# OctoSlime_TouchPad_Led_Mount.net
KiCad netlist of a schematic drawn in EasyEDA Pro
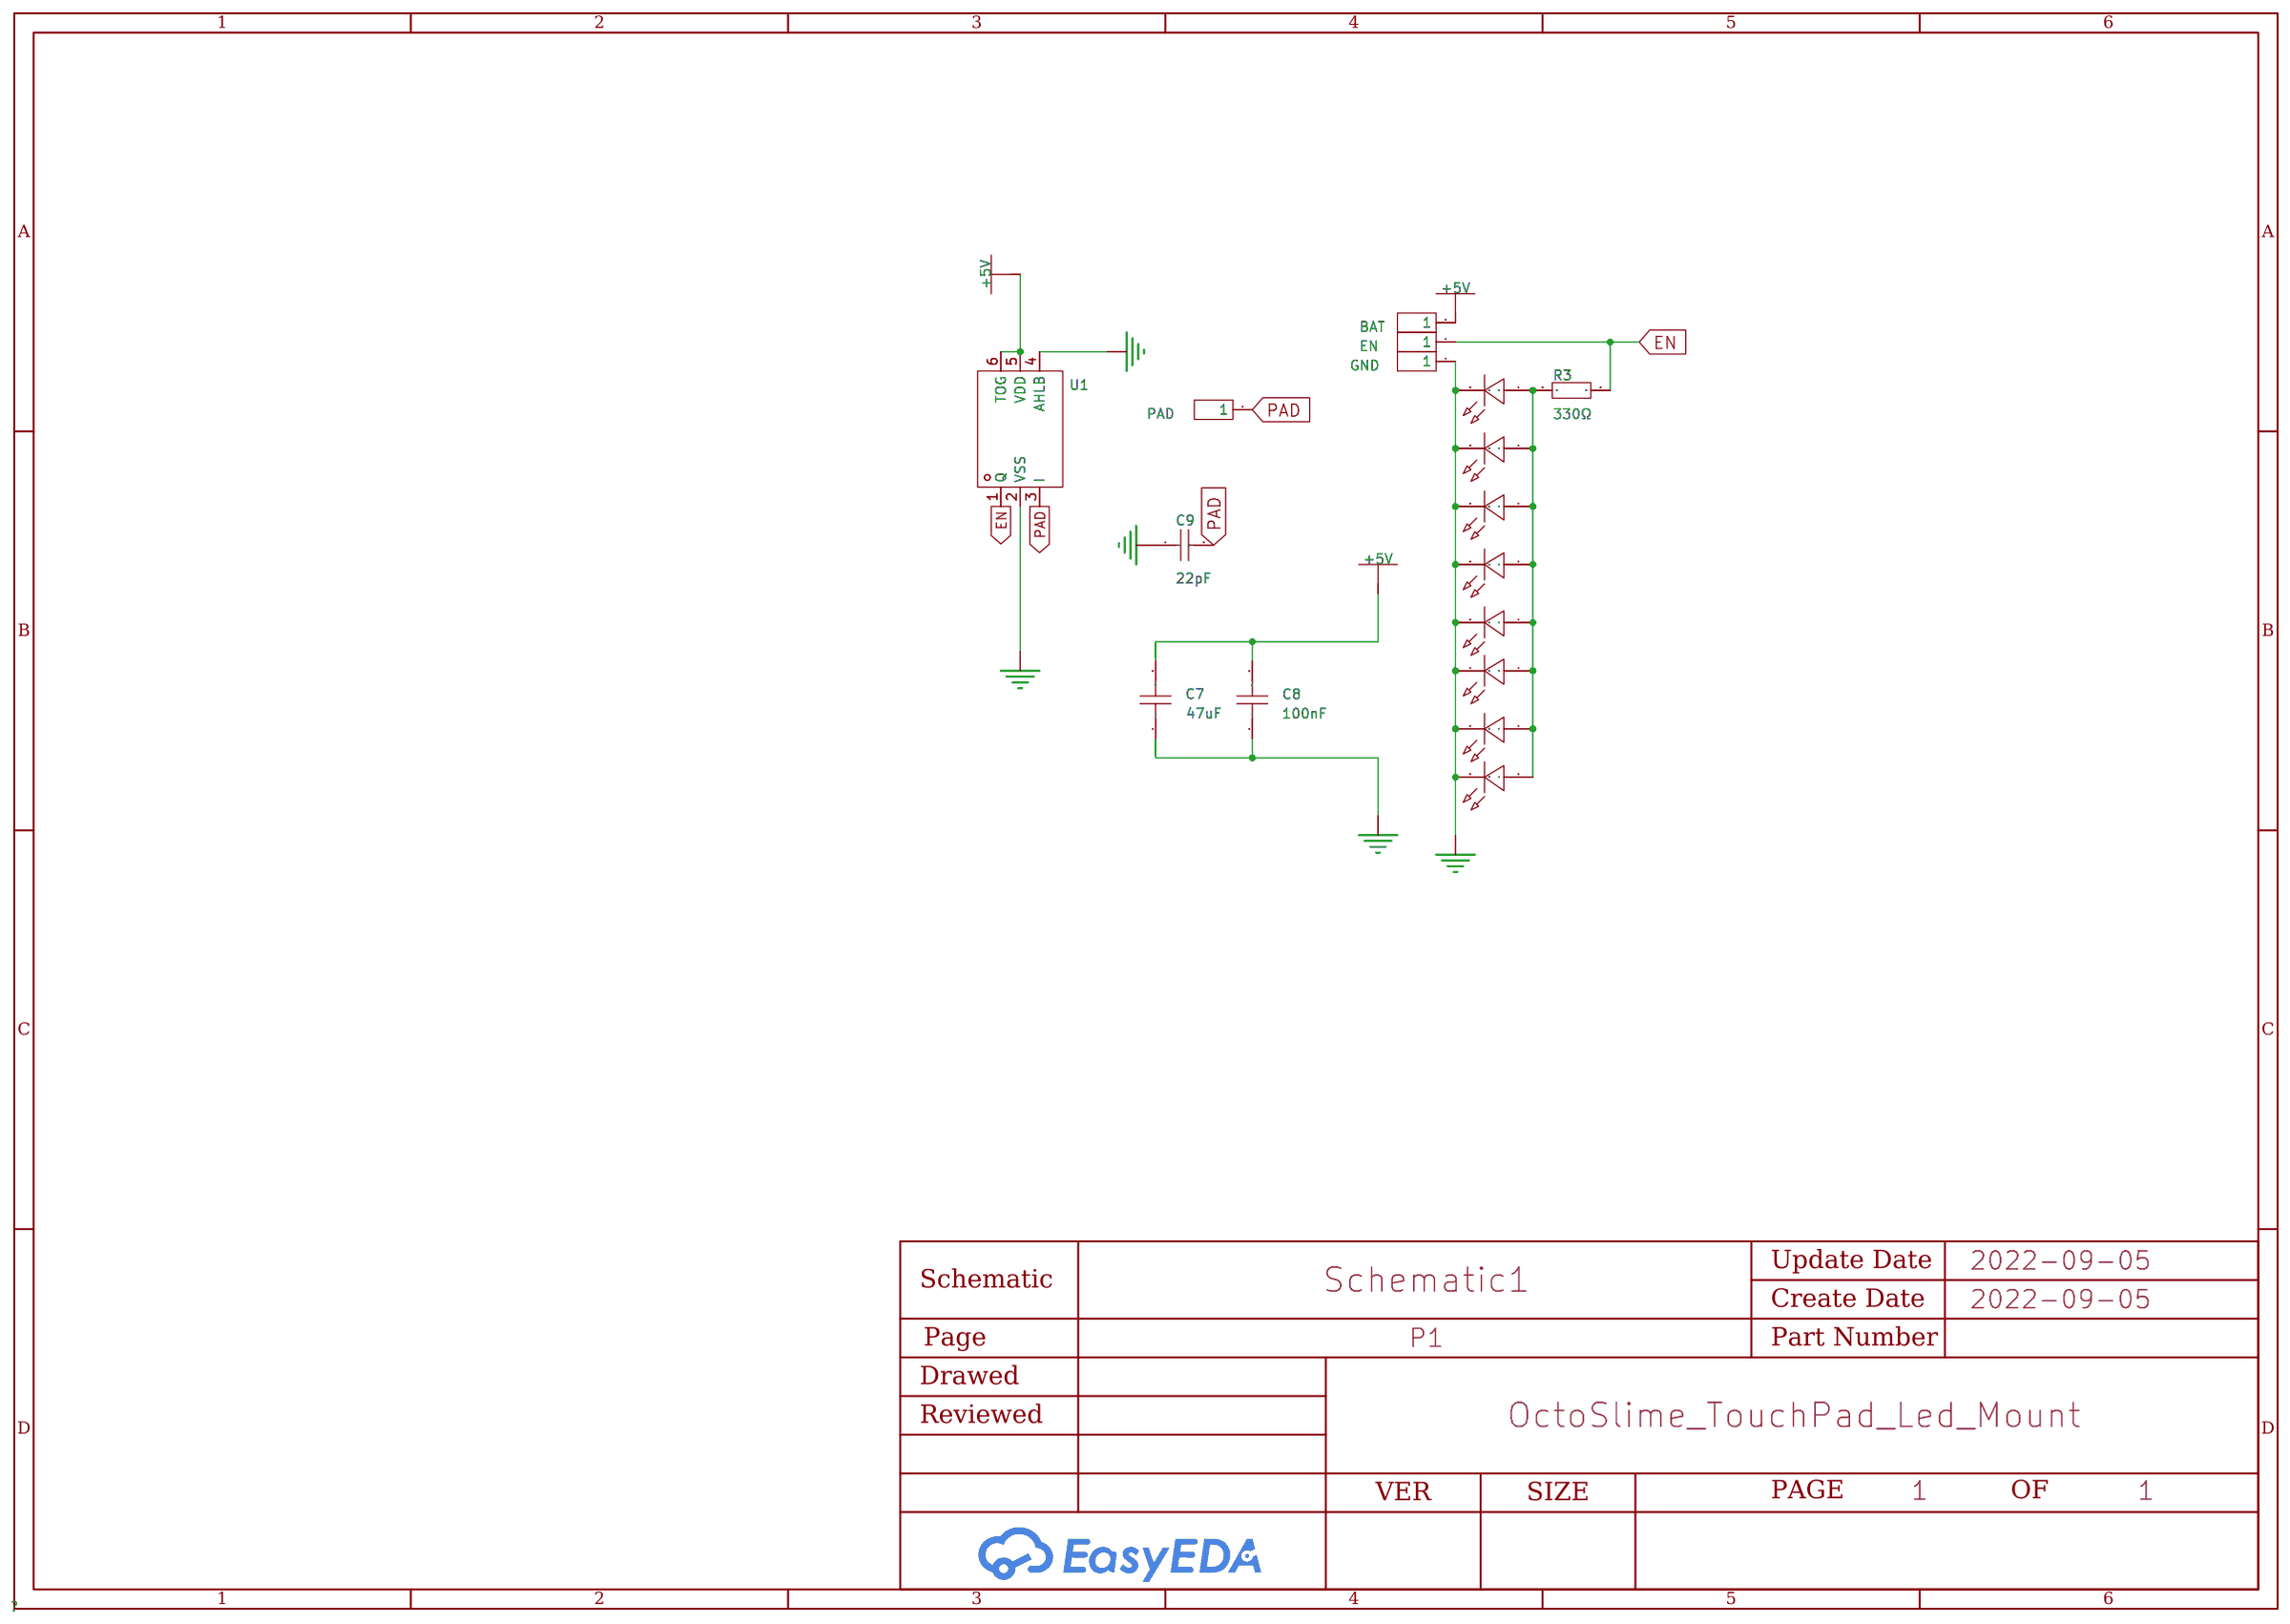
[diagram p0: schematic sheet]

(export (version "E")
  (design (tool "Eeschema 10.0.6"))
  (components
    (comp (ref "BAT")
      (value "~")
      (footprint "easyedapro:HDR-TH_1P-P2.54-V-M")
      (description "间距:-;总PIN位数:1;排数:1;插针结构:-;行距:-;安装类型:直插;圆针/方针:-;额定电流:-;额定电压:-;配合针长度:-;塑高:-;触头材质:-;触头镀层:-;颜色:黑色;")
      (fields (field (name "Manufacturer Part") "2.54-1*1P针") (field (name "Manufacturer") "BOOMELE(博穆精密)"))
      (libsource (lib "easyedapro") (part "Header-Male-2.54_1x1"))
    )
    (comp (ref "C7")
      (value "47uF")
      (footprint "easyedapro:C1206")
      (description "容值:47uF;精度:±20%;额定电压:10V;温度系数:X5R;")
      (fields
        (field (name "Manufacturer Part") "CL31A476MPHNNNE")
        (field (name "Manufacturer") "SAMSUNG(三星)")
      )
      (libsource (lib "easyedapro") (part "CL31A476MPHNNNE"))
    )
    (comp (ref "C8")
      (value "100nF")
      (footprint "easyedapro:C0402")
      (description "容值:100nF;精度:±10%;额定电压:50V;温度系数:X7R;")
      (fields
        (field (name "Manufacturer Part") "CL05B104KB54PNC")
        (field (name "Manufacturer") "SAMSUNG(三星)")
      )
      (libsource (lib "easyedapro") (part "CL05B104KB54PNC"))
    )
    (comp (ref "C9")
      (value "22pF")
      (footprint "easyedapro:C0805")
      (description "容值:22pF;精度:±5%;额定电压:50V;温度系数:C0G;")
      (fields
        (field (name "Manufacturer Part") "CL21C220JBANNNC")
        (field (name "Manufacturer") "SAMSUNG(三星)")
      )
      (libsource (lib "easyedapro") (part "CL21C220JBANNNC"))
    )
    (comp (ref "EN")
      (value "~")
      (footprint "easyedapro:HDR-TH_1P-P2.54-V-M")
      (description "间距:-;总PIN位数:1;排数:1;插针结构:-;行距:-;安装类型:直插;圆针/方针:-;额定电流:-;额定电压:-;配合针长度:-;塑高:-;触头材质:-;触头镀层:-;颜色:黑色;")
      (fields (field (name "Manufacturer Part") "2.54-1*1P针") (field (name "Manufacturer") "BOOMELE(博穆精密)"))
      (libsource (lib "easyedapro") (part "Header-Male-2.54_1x1"))
    )
    (comp (ref "GND")
      (value "~")
      (footprint "easyedapro:HDR-TH_1P-P2.54-V-M")
      (description "间距:-;总PIN位数:1;排数:1;插针结构:-;行距:-;安装类型:直插;圆针/方针:-;额定电流:-;额定电压:-;配合针长度:-;塑高:-;触头材质:-;触头镀层:-;颜色:黑色;")
      (fields (field (name "Manufacturer Part") "2.54-1*1P针") (field (name "Manufacturer") "BOOMELE(博穆精密)"))
      (libsource (lib "easyedapro") (part "Header-Male-2.54_1x1"))
    )
    (comp (ref "LED5")
      (value "LED-0805_B")
      (footprint "easyedapro:LED0805_BLUE")
      (fields (field (name "Manufacturer Part") "D-B080508B1-KS2") (field (name "Manufacturer") "方舟 ARKLED"))
      (libsource (lib "easyedapro") (part "LED-0805_B"))
    )
    (comp (ref "LED6")
      (value "LED-0805_B")
      (footprint "easyedapro:LED0805_BLUE")
      (fields (field (name "Manufacturer Part") "D-B080508B1-KS2") (field (name "Manufacturer") "方舟 ARKLED"))
      (libsource (lib "easyedapro") (part "LED-0805_B"))
    )
    (comp (ref "LED7")
      (value "LED-0805_B")
      (footprint "easyedapro:LED0805_BLUE")
      (fields (field (name "Manufacturer Part") "D-B080508B1-KS2") (field (name "Manufacturer") "方舟 ARKLED"))
      (libsource (lib "easyedapro") (part "LED-0805_B"))
    )
    (comp (ref "LED8")
      (value "LED-0805_B")
      (footprint "easyedapro:LED0805_BLUE")
      (fields (field (name "Manufacturer Part") "D-B080508B1-KS2") (field (name "Manufacturer") "方舟 ARKLED"))
      (libsource (lib "easyedapro") (part "LED-0805_B"))
    )
    (comp (ref "LED9")
      (value "LED-0805_B")
      (footprint "easyedapro:LED0805_BLUE")
      (fields (field (name "Manufacturer Part") "D-B080508B1-KS2") (field (name "Manufacturer") "方舟 ARKLED"))
      (libsource (lib "easyedapro") (part "LED-0805_B"))
    )
    (comp (ref "LED10")
      (value "LED-0805_B")
      (footprint "easyedapro:LED0805_BLUE")
      (fields (field (name "Manufacturer Part") "D-B080508B1-KS2") (field (name "Manufacturer") "方舟 ARKLED"))
      (libsource (lib "easyedapro") (part "LED-0805_B"))
    )
    (comp (ref "LED11")
      (value "LED-0805_B")
      (footprint "easyedapro:LED0805_BLUE")
      (fields (field (name "Manufacturer Part") "D-B080508B1-KS2") (field (name "Manufacturer") "方舟 ARKLED"))
      (libsource (lib "easyedapro") (part "LED-0805_B"))
    )
    (comp (ref "LED12")
      (value "LED-0805_B")
      (footprint "easyedapro:LED0805_BLUE")
      (fields (field (name "Manufacturer Part") "D-B080508B1-KS2") (field (name "Manufacturer") "方舟 ARKLED"))
      (libsource (lib "easyedapro") (part "LED-0805_B"))
    )
    (comp (ref "PAD")
      (value "~")
      (footprint "easyedapro:HDR-TH_1P-P2.54-V-M")
      (description "间距:-;总PIN位数:1;排数:1;插针结构:-;行距:-;安装类型:直插;圆针/方针:-;额定电流:-;额定电压:-;配合针长度:-;塑高:-;触头材质:-;触头镀层:-;颜色:黑色;")
      (fields (field (name "Manufacturer Part") "2.54-1*1P针") (field (name "Manufacturer") "BOOMELE(博穆精密)"))
      (libsource (lib "easyedapro") (part "Header-Male-2.54_1x1"))
    )
    (comp (ref "R3")
      (value "330Ω")
      (footprint "easyedapro:R0805")
      (description "电阻类型:厚膜电阻;阻值:330Ω;精度:±1%;功率:125mW;温度系数:±100ppm/;最大工作电压:150V;工作温度范围:-55~+155;")
      (fields
        (field (name "Manufacturer Part") "0805W8F3300T5E")
        (field (name "Manufacturer") "UNI-ROYAL(厚声)")
      )
      (libsource (lib "easyedapro") (part "0805W8F3300T5E"))
    )
    (comp (ref "U1")
      (value "~")
      (footprint "easyedapro:SOT-23-6_L2.9-W1.6-P0.95-LS2.8-BR")
      (description "单按键触摸感应开关")
      (fields (field (name "Manufacturer Part") "TTP223E-BA6") (field (name "Manufacturer") "TONTEK(台湾通泰)"))
      (libsource (lib "easyedapro") (part "TTP223E-BA6"))
    )
  )
  (nets
    (net (code "1") (name "+5V") (class "Default")
      (node (ref "BAT") (pin "1") (pinfunction "1_1") (pintype "input"))
      (node (ref "C7") (pin "2") (pinfunction "2_2") (pintype "input"))
      (node (ref "C8") (pin "2") (pinfunction "2_2") (pintype "input"))
      (node (ref "U1") (pin "5") (pinfunction "VDD_5") (pintype "input"))
      (node (ref "U1") (pin "6") (pinfunction "TOG_6") (pintype "input"))
    )
    (net (code "2") (name "EN") (class "Default")
      (node (ref "EN") (pin "1") (pinfunction "1_1") (pintype "input"))
      (node (ref "R3") (pin "1") (pinfunction "1_1") (pintype "input"))
      (node (ref "U1") (pin "1") (pinfunction "Q_1") (pintype "input"))
    )
    (net (code "3") (name "GND") (class "Default")
      (node (ref "C7") (pin "1") (pinfunction "1_1") (pintype "input"))
      (node (ref "C8") (pin "1") (pinfunction "1_1") (pintype "input"))
      (node (ref "C9") (pin "1") (pinfunction "1_1") (pintype "input"))
      (node (ref "GND") (pin "1") (pinfunction "1_1") (pintype "input"))
      (node (ref "LED10") (pin "2") (pinfunction "2_2") (pintype "input"))
      (node (ref "LED11") (pin "2") (pinfunction "2_2") (pintype "input"))
      (node (ref "LED12") (pin "2") (pinfunction "2_2") (pintype "input"))
      (node (ref "LED5") (pin "2") (pinfunction "2_2") (pintype "input"))
      (node (ref "LED6") (pin "2") (pinfunction "2_2") (pintype "input"))
      (node (ref "LED7") (pin "2") (pinfunction "2_2") (pintype "input"))
      (node (ref "LED8") (pin "2") (pinfunction "2_2") (pintype "input"))
      (node (ref "LED9") (pin "2") (pinfunction "2_2") (pintype "input"))
      (node (ref "U1") (pin "2") (pinfunction "VSS_2") (pintype "input"))
      (node (ref "U1") (pin "4") (pinfunction "AHLB_4") (pintype "input"))
    )
    (net (code "4") (name "Net-(LED10-Pad1)") (class "Default")
      (node (ref "LED10") (pin "1") (pinfunction "1_1") (pintype "input"))
      (node (ref "LED11") (pin "1") (pinfunction "1_1") (pintype "input"))
      (node (ref "LED12") (pin "1") (pinfunction "1_1") (pintype "input"))
      (node (ref "LED5") (pin "1") (pinfunction "1_1") (pintype "input"))
      (node (ref "LED6") (pin "1") (pinfunction "1_1") (pintype "input"))
      (node (ref "LED7") (pin "1") (pinfunction "1_1") (pintype "input"))
      (node (ref "LED8") (pin "1") (pinfunction "1_1") (pintype "input"))
      (node (ref "LED9") (pin "1") (pinfunction "1_1") (pintype "input"))
      (node (ref "R3") (pin "2") (pinfunction "2_2") (pintype "input"))
    )
    (net (code "5") (name "PAD") (class "Default")
      (node (ref "C9") (pin "2") (pinfunction "2_2") (pintype "input"))
      (node (ref "PAD") (pin "1") (pinfunction "1_1") (pintype "input"))
      (node (ref "U1") (pin "3") (pinfunction "I_3") (pintype "input"))
    )
  )
)
